# Sheet1.net
KiCad netlist of a schematic drawn in Altium Designer
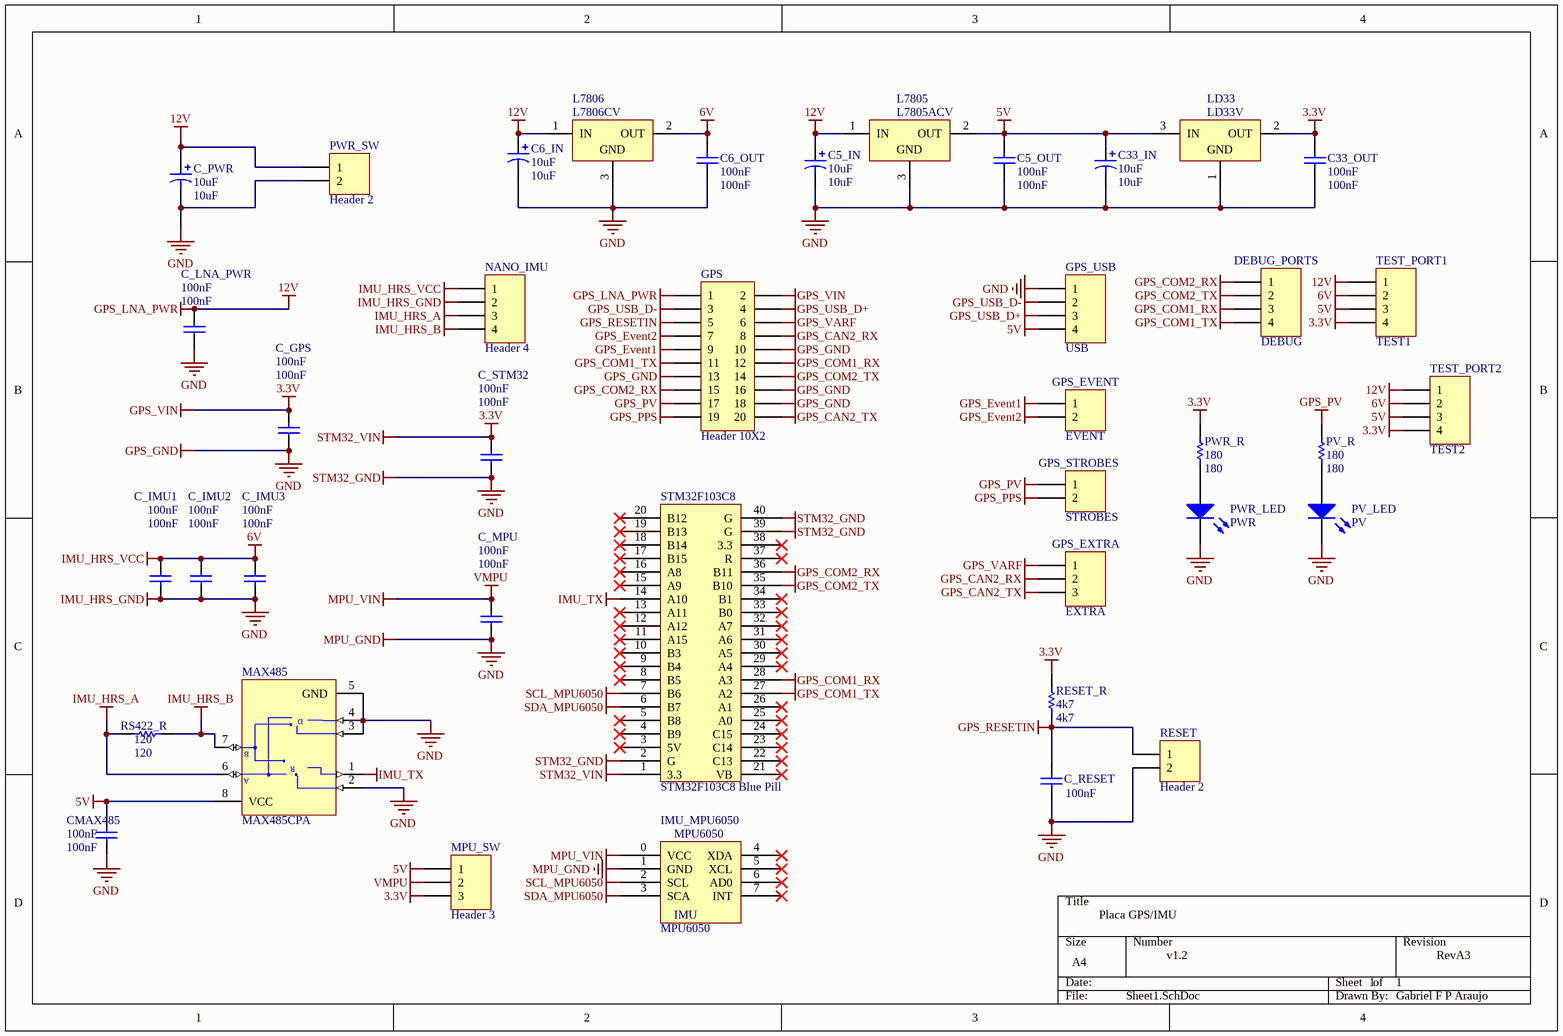
[diagram p0: Sheet1.SchDoc]

(export (version "E")
  (design (tool "Eeschema 10.0.6"))
  (components
    (comp (ref "C5_IN")
      (value "10uF")
      (footprint "Capacitor1")
      (description "Polarized Capacitor (Radial)")
      (fields (field (name "ALTIUM_VALUE") "10uF") (field (name "PUBLISHER") "Altium Limited"))
      (libsource (lib "Miscellaneous Devices") (part "Cap Pol1"))
    )
    (comp (ref "C5_OUT")
      (value "100nF")
      (footprint "C_NANO_HOLES")
      (description "Capacitor")
      (fields (field (name "ALTIUM_VALUE") "100nF") (field (name "PUBLISHER") "Altium Limited"))
      (libsource (lib "Miscellaneous Devices") (part "Cap"))
    )
    (comp (ref "C6_IN")
      (value "10uF")
      (footprint "Capacitor1")
      (description "Polarized Capacitor (Radial)")
      (fields (field (name "ALTIUM_VALUE") "10uF") (field (name "PUBLISHER") "Altium Limited"))
      (libsource (lib "Miscellaneous Devices") (part "Cap Pol1"))
    )
    (comp (ref "C6_OUT")
      (value "100nF")
      (footprint "C_NANO_HOLES")
      (description "Capacitor")
      (fields (field (name "ALTIUM_VALUE") "100nF") (field (name "PUBLISHER") "Altium Limited"))
      (libsource (lib "Miscellaneous Devices") (part "Cap"))
    )
    (comp (ref "C33_IN")
      (value "10uF")
      (footprint "Capacitor1")
      (description "Polarized Capacitor (Radial)")
      (fields (field (name "ALTIUM_VALUE") "10uF") (field (name "PUBLISHER") "Altium Limited"))
      (libsource (lib "Miscellaneous Devices") (part "Cap Pol1"))
    )
    (comp (ref "C33_OUT")
      (value "100nF")
      (footprint "C_NANO_HOLES")
      (description "Capacitor")
      (fields (field (name "ALTIUM_VALUE") "100nF") (field (name "PUBLISHER") "Altium Limited"))
      (libsource (lib "Miscellaneous Devices") (part "Cap"))
    )
    (comp (ref "CMAX485")
      (value "100nF")
      (footprint "C_NANO_HOLES")
      (description "Capacitor")
      (fields (field (name "ALTIUM_VALUE") "100nF") (field (name "PUBLISHER") "Altium Limited"))
      (libsource (lib "Miscellaneous Devices") (part "Cap"))
    )
    (comp (ref "C_GPS")
      (value "100nF")
      (footprint "C_NANO_HOLES")
      (description "Capacitor")
      (fields (field (name "ALTIUM_VALUE") "100nF") (field (name "PUBLISHER") "Altium Limited"))
      (libsource (lib "Miscellaneous Devices") (part "Cap"))
    )
    (comp (ref "C_IMU1")
      (value "100nF")
      (footprint "C_NANO_HOLES")
      (description "Capacitor")
      (fields (field (name "ALTIUM_VALUE") "100nF") (field (name "PUBLISHER") "Altium Limited"))
      (libsource (lib "Miscellaneous Devices") (part "Cap"))
    )
    (comp (ref "C_IMU2")
      (value "100nF")
      (footprint "C_NANO_HOLES")
      (description "Capacitor")
      (fields (field (name "ALTIUM_VALUE") "100nF") (field (name "PUBLISHER") "Altium Limited"))
      (libsource (lib "Miscellaneous Devices") (part "Cap"))
    )
    (comp (ref "C_IMU3")
      (value "100nF")
      (footprint "C_NANO_HOLES")
      (description "Capacitor")
      (fields (field (name "ALTIUM_VALUE") "100nF") (field (name "PUBLISHER") "Altium Limited"))
      (libsource (lib "Miscellaneous Devices") (part "Cap"))
    )
    (comp (ref "C_LNA_PWR")
      (value "100nF")
      (footprint "C_NANO_HOLES")
      (description "Capacitor")
      (fields (field (name "ALTIUM_VALUE") "100nF") (field (name "PUBLISHER") "Altium Limited"))
      (libsource (lib "Miscellaneous Devices") (part "Cap"))
    )
    (comp (ref "C_MPU")
      (value "100nF")
      (footprint "C_NANO_HOLES")
      (description "Capacitor")
      (fields (field (name "ALTIUM_VALUE") "100nF") (field (name "PUBLISHER") "Altium Limited"))
      (libsource (lib "Miscellaneous Devices") (part "Cap"))
    )
    (comp (ref "C_PWR")
      (value "10uF")
      (footprint "Capacitor1")
      (description "Polarized Capacitor (Radial)")
      (fields (field (name "ALTIUM_VALUE") "10uF") (field (name "PUBLISHER") "Altium Limited"))
      (libsource (lib "Miscellaneous Devices") (part "Cap Pol1"))
    )
    (comp (ref "C_RESET")
      (value "100nF")
      (footprint "C_NANO_HOLES")
      (description "Capacitor")
      (fields (field (name "PUBLISHER") "Altium Limited"))
      (libsource (lib "Miscellaneous Devices") (part "Cap"))
    )
    (comp (ref "C_STM32")
      (value "100nF")
      (footprint "C_NANO_HOLES")
      (description "Capacitor")
      (fields (field (name "ALTIUM_VALUE") "100nF") (field (name "PUBLISHER") "Altium Limited"))
      (libsource (lib "Miscellaneous Devices") (part "Cap"))
    )
    (comp (ref "DEBUG_PORTS")
      (value "DEBUG")
      (footprint "HDR1X4")
      (description "Header, 4-Pin")
      (fields (field (name "PUBLISHER") "Altium Limited"))
      (libsource (lib "Miscellaneous Connectors") (part "Header 4"))
    )
    (comp (ref "GPS")
      (value "Header 10X2")
      (footprint "HDR2x10_2mm")
      (description "Header, 10-Pin, Dual row")
      (fields (field (name "PUBLISHER") "Altium Limited"))
      (libsource (lib "Miscellaneous Connectors") (part "Header 10X2"))
    )
    (comp (ref "GPS_EVENT")
      (value "EVENT")
      (footprint "HDR1X2")
      (description "Header, 2-Pin")
      (fields (field (name "PUBLISHER") "Altium Limited"))
      (libsource (lib "Miscellaneous Connectors") (part "Header 2"))
    )
    (comp (ref "GPS_EXTRA")
      (value "EXTRA")
      (footprint "HDR1X3")
      (description "Header, 3-Pin")
      (fields (field (name "PUBLISHER") "Altium Limited"))
      (libsource (lib "Miscellaneous Connectors") (part "Header 3"))
    )
    (comp (ref "GPS_STROBES")
      (value "STROBES")
      (footprint "HDR1X2")
      (description "Header, 2-Pin")
      (fields (field (name "PUBLISHER") "Altium Limited"))
      (libsource (lib "Miscellaneous Connectors") (part "Header 2"))
    )
    (comp (ref "GPS_USB")
      (value "USB")
      (footprint "HDR1X4")
      (description "Header, 4-Pin")
      (fields (field (name "PUBLISHER") "Altium Limited"))
      (libsource (lib "Miscellaneous Connectors") (part "Header 4"))
    )
    (comp (ref "IMU_MPU6050")
      (value "MPU6050")
      (footprint "MPU6050")
      (libsource (lib "IMU_MPU6050") (part "Component_1"))
    )
    (comp (ref "L7805")
      (value "L7805ACV")
      (footprint "TO220ABN")
      (description "Precision 1A Regulator")
      (fields (field (name "PUBLISHER") "Altium Limited"))
      (libsource (lib "ST Power Mgt Voltage Regulator") (part "L7805ACV"))
    )
    (comp (ref "L7806")
      (value "L7806CV")
      (footprint "TO220ABN")
      (description "Positive Voltage Regulator")
      (fields (field (name "PUBLISHER") "Altium Limited"))
      (libsource (lib "ST Power Mgt Voltage Regulator") (part "L7806CV"))
    )
    (comp (ref "LD33")
      (value "LD33V")
      (footprint "T03B")
      (description "800mA Low-Dropout Linear Regulator")
      (fields
        (field (name "PARTNUMBER") "LM1117T-3.3")
        (field (name "MANUFACTURER") "National Semiconductor")
        (field (name "PUBLISHER") "Altium Limited")
      )
      (libsource (lib "NSC LDO") (part "LM1117T-3.3"))
    )
    (comp (ref "MAX485")
      (value "MAX485CPA")
      (footprint "PA8")
      (description "Low-Power, Slew-Rate-Limited RS-485/RS-422 Transceiver")
      (fields (field (name "PUBLISHER") "Altium Limited"))
      (libsource (lib "Maxim Communication Transceiver") (part "MAX485CPA"))
    )
    (comp (ref "MPU_SW")
      (value "Header 3")
      (footprint "HDR1X3")
      (description "Header, 3-Pin")
      (fields (field (name "PUBLISHER") "Altium Limited"))
      (libsource (lib "Miscellaneous Connectors") (part "Header 3"))
    )
    (comp (ref "NANO_IMU")
      (value "Header 4")
      (footprint "HDR1X4")
      (description "Header, 4-Pin")
      (fields (field (name "PUBLISHER") "Altium Limited"))
      (libsource (lib "Miscellaneous Connectors") (part "Header 4"))
    )
    (comp (ref "PV_LED")
      (value "PV")
      (footprint "HDR1X2")
      (description "Typical INFRARED GaAs LED")
      (fields (field (name "PUBLISHER") "Altium Limited"))
      (libsource (lib "Miscellaneous Devices") (part "LED0"))
    )
    (comp (ref "PV_R")
      (value "180")
      (footprint "AXIAL-0.3")
      (description "Resistor")
      (fields (field (name "ALTIUM_VALUE") "180") (field (name "PUBLISHER") "Altium Limited"))
      (libsource (lib "Miscellaneous Devices") (part "Res1"))
    )
    (comp (ref "PWR_LED")
      (value "PWR")
      (footprint "HDR1X2")
      (description "Typical INFRARED GaAs LED")
      (fields (field (name "PUBLISHER") "Altium Limited"))
      (libsource (lib "Miscellaneous Devices") (part "LED0"))
    )
    (comp (ref "PWR_R")
      (value "180")
      (footprint "AXIAL-0.3")
      (description "Resistor")
      (fields (field (name "ALTIUM_VALUE") "180") (field (name "PUBLISHER") "Altium Limited"))
      (libsource (lib "Miscellaneous Devices") (part "Res1"))
    )
    (comp (ref "PWR_SW")
      (value "Header 2")
      (footprint "HDR1X2")
      (description "Header, 2-Pin")
      (fields (field (name "PUBLISHER") "Altium Limited"))
      (libsource (lib "Miscellaneous Connectors") (part "Header 2"))
    )
    (comp (ref "RESET")
      (value "Header 2")
      (footprint "HDR1X2")
      (description "Header, 2-Pin")
      (fields (field (name "PUBLISHER") "Altium Limited"))
      (libsource (lib "Miscellaneous Connectors") (part "Header 2"))
    )
    (comp (ref "RESET_R")
      (value "4k7")
      (footprint "AXIAL-0.3")
      (description "Resistor")
      (fields (field (name "ALTIUM_VALUE") "4k7") (field (name "PUBLISHER") "Altium Limited"))
      (libsource (lib "Miscellaneous Devices") (part "Res1"))
    )
    (comp (ref "RS422_R")
      (value "120")
      (footprint "AXIAL-0.3")
      (description "Resistor")
      (fields (field (name "ALTIUM_VALUE") "120") (field (name "PUBLISHER") "Altium Limited"))
      (libsource (lib "Miscellaneous Devices") (part "Res1"))
    )
    (comp (ref "STM32F103C8")
      (value "STM32F103C8 Blue Pill")
      (footprint "STM32F103C8")
      (libsource (lib "BluePill") (part "STM32F103C8"))
    )
    (comp (ref "TEST_PORT1")
      (value "TEST1")
      (footprint "HDR1X4")
      (description "Header, 4-Pin")
      (fields (field (name "PUBLISHER") "Altium Limited"))
      (libsource (lib "Miscellaneous Connectors") (part "Header 4"))
    )
    (comp (ref "TEST_PORT2")
      (value "TEST2")
      (footprint "HDR1X4")
      (description "Header, 4-Pin")
      (fields (field (name "PUBLISHER") "Altium Limited"))
      (libsource (lib "Miscellaneous Connectors") (part "Header 4"))
    )
  )
  (nets
    (net (code "1") (name "3.3V") (class "Default")
      (node (ref "C33_OUT") (pin "1") (pinfunction "1_1") (pintype "passive"))
      (node (ref "C_GPS") (pin "2") (pinfunction "2_2") (pintype "passive"))
      (node (ref "C_STM32") (pin "2") (pinfunction "2_2") (pintype "passive"))
      (node (ref "GPS") (pin "2") (pinfunction "2_2") (pintype "passive"))
      (node (ref "LD33") (pin "2") (pinfunction "OUT_2") (pintype "power_in"))
      (node (ref "MPU_SW") (pin "3") (pinfunction "3_3") (pintype "passive"))
      (node (ref "PWR_R") (pin "2") (pinfunction "2_2") (pintype "passive"))
      (node (ref "RESET_R") (pin "2") (pinfunction "2_2") (pintype "passive"))
      (node (ref "STM32F103C8") (pin "1") (pinfunction "3.3_1") (pintype "passive"))
      (node (ref "TEST_PORT1") (pin "4") (pinfunction "4_4") (pintype "passive"))
      (node (ref "TEST_PORT2") (pin "4") (pinfunction "4_4") (pintype "passive"))
    )
    (net (code "2") (name "5V") (class "Default")
      (node (ref "C33_IN") (pin "1") (pinfunction "1_1") (pintype "passive"))
      (node (ref "C5_OUT") (pin "1") (pinfunction "1_1") (pintype "passive"))
      (node (ref "CMAX485") (pin "2") (pinfunction "2_2") (pintype "passive"))
      (node (ref "GPS_USB") (pin "4") (pinfunction "4_4") (pintype "passive"))
      (node (ref "L7805") (pin "2") (pinfunction "OUT_2") (pintype "power_in"))
      (node (ref "LD33") (pin "3") (pinfunction "IN_3") (pintype "power_in"))
      (node (ref "MAX485") (pin "8") (pinfunction "VCC_8") (pintype "power_in"))
      (node (ref "MPU_SW") (pin "1") (pinfunction "1_1") (pintype "passive"))
      (node (ref "TEST_PORT1") (pin "3") (pinfunction "3_3") (pintype "passive"))
      (node (ref "TEST_PORT2") (pin "3") (pinfunction "3_3") (pintype "passive"))
    )
    (net (code "3") (name "6V") (class "Default")
      (node (ref "C6_OUT") (pin "1") (pinfunction "1_1") (pintype "passive"))
      (node (ref "C_IMU1") (pin "2") (pinfunction "2_2") (pintype "passive"))
      (node (ref "C_IMU2") (pin "2") (pinfunction "2_2") (pintype "passive"))
      (node (ref "C_IMU3") (pin "2") (pinfunction "2_2") (pintype "passive"))
      (node (ref "L7806") (pin "2") (pinfunction "OUT_2") (pintype "power_in"))
      (node (ref "NANO_IMU") (pin "1") (pinfunction "1_1") (pintype "passive"))
      (node (ref "TEST_PORT1") (pin "2") (pinfunction "2_2") (pintype "passive"))
      (node (ref "TEST_PORT2") (pin "2") (pinfunction "2_2") (pintype "passive"))
    )
    (net (code "4") (name "12V") (class "Default")
      (node (ref "C5_IN") (pin "1") (pinfunction "1_1") (pintype "passive"))
      (node (ref "C6_IN") (pin "1") (pinfunction "1_1") (pintype "passive"))
      (node (ref "C_LNA_PWR") (pin "2") (pinfunction "2_2") (pintype "passive"))
      (node (ref "C_PWR") (pin "1") (pinfunction "1_1") (pintype "passive"))
      (node (ref "GPS") (pin "1") (pinfunction "1_1") (pintype "passive"))
      (node (ref "L7805") (pin "1") (pinfunction "IN_1") (pintype "power_in"))
      (node (ref "L7806") (pin "1") (pinfunction "IN_1") (pintype "power_in"))
      (node (ref "PWR_SW") (pin "1") (pinfunction "1_1") (pintype "passive"))
      (node (ref "TEST_PORT1") (pin "1") (pinfunction "1_1") (pintype "passive"))
      (node (ref "TEST_PORT2") (pin "1") (pinfunction "1_1") (pintype "passive"))
    )
    (net (code "5") (name "GND") (class "Default")
      (node (ref "C33_IN") (pin "2") (pinfunction "2_2") (pintype "passive"))
      (node (ref "C33_OUT") (pin "2") (pinfunction "2_2") (pintype "passive"))
      (node (ref "C5_IN") (pin "2") (pinfunction "2_2") (pintype "passive"))
      (node (ref "C5_OUT") (pin "2") (pinfunction "2_2") (pintype "passive"))
      (node (ref "C6_IN") (pin "2") (pinfunction "2_2") (pintype "passive"))
      (node (ref "C6_OUT") (pin "2") (pinfunction "2_2") (pintype "passive"))
      (node (ref "CMAX485") (pin "1") (pinfunction "1_1") (pintype "passive"))
      (node (ref "C_GPS") (pin "1") (pinfunction "1_1") (pintype "passive"))
      (node (ref "C_IMU1") (pin "1") (pinfunction "1_1") (pintype "passive"))
      (node (ref "C_IMU2") (pin "1") (pinfunction "1_1") (pintype "passive"))
      (node (ref "C_IMU3") (pin "1") (pinfunction "1_1") (pintype "passive"))
      (node (ref "C_LNA_PWR") (pin "1") (pinfunction "1_1") (pintype "passive"))
      (node (ref "C_MPU") (pin "1") (pinfunction "1_1") (pintype "passive"))
      (node (ref "C_PWR") (pin "2") (pinfunction "2_2") (pintype "passive"))
      (node (ref "C_RESET") (pin "1") (pinfunction "1_1") (pintype "passive"))
      (node (ref "C_STM32") (pin "1") (pinfunction "1_1") (pintype "passive"))
      (node (ref "GPS") (pin "10") (pinfunction "10_10") (pintype "passive"))
      (node (ref "GPS") (pin "13") (pinfunction "13_13") (pintype "passive"))
      (node (ref "GPS") (pin "16") (pinfunction "16_16") (pintype "passive"))
      (node (ref "GPS") (pin "18") (pinfunction "18_18") (pintype "passive"))
      (node (ref "GPS_USB") (pin "1") (pinfunction "1_1") (pintype "passive"))
      (node (ref "IMU_MPU6050") (pin "1") (pinfunction "GND_1") (pintype "passive"))
      (node (ref "L7805") (pin "3") (pinfunction "GND_3") (pintype "power_in"))
      (node (ref "L7806") (pin "3") (pinfunction "GND_3") (pintype "power_in"))
      (node (ref "LD33") (pin "1") (pinfunction "GND_1") (pintype "power_in"))
      (node (ref "MAX485") (pin "2") (pinfunction "~{RE}_2") (pintype "input"))
      (node (ref "MAX485") (pin "3") (pinfunction "DE_3") (pintype "input"))
      (node (ref "MAX485") (pin "4") (pinfunction "DI_4") (pintype "input"))
      (node (ref "MAX485") (pin "5") (pinfunction "GND_5") (pintype "power_in"))
      (node (ref "NANO_IMU") (pin "2") (pinfunction "2_2") (pintype "passive"))
      (node (ref "PV_LED") (pin "2") (pinfunction "K_2") (pintype "passive"))
      (node (ref "PWR_LED") (pin "2") (pinfunction "K_2") (pintype "passive"))
      (node (ref "PWR_SW") (pin "2") (pinfunction "2_2") (pintype "passive"))
      (node (ref "RESET") (pin "2") (pinfunction "2_2") (pintype "passive"))
      (node (ref "STM32F103C8") (pin "2") (pinfunction "G_2") (pintype "passive"))
      (node (ref "STM32F103C8") (pin "39") (pinfunction "G_39") (pintype "passive"))
      (node (ref "STM32F103C8") (pin "40") (pinfunction "G_40") (pintype "passive"))
    )
    (net (code "6") (name "GPS_CAN2_RX") (class "Default")
      (node (ref "GPS") (pin "8") (pinfunction "8_8") (pintype "passive"))
      (node (ref "GPS_EXTRA") (pin "2") (pinfunction "2_2") (pintype "passive"))
    )
    (net (code "7") (name "GPS_CAN2_TX") (class "Default")
      (node (ref "GPS") (pin "20") (pinfunction "20_20") (pintype "passive"))
      (node (ref "GPS_EXTRA") (pin "3") (pinfunction "3_3") (pintype "passive"))
    )
    (net (code "8") (name "GPS_COM1_RX") (class "Default")
      (node (ref "DEBUG_PORTS") (pin "3") (pinfunction "3_3") (pintype "passive"))
      (node (ref "GPS") (pin "12") (pinfunction "12_12") (pintype "passive"))
      (node (ref "STM32F103C8") (pin "28") (pinfunction "A3_28") (pintype "passive"))
    )
    (net (code "9") (name "GPS_COM1_TX") (class "Default")
      (node (ref "DEBUG_PORTS") (pin "4") (pinfunction "4_4") (pintype "passive"))
      (node (ref "GPS") (pin "11") (pinfunction "11_11") (pintype "passive"))
      (node (ref "STM32F103C8") (pin "27") (pinfunction "A2_27") (pintype "passive"))
    )
    (net (code "10") (name "GPS_COM2_RX") (class "Default")
      (node (ref "DEBUG_PORTS") (pin "1") (pinfunction "1_1") (pintype "passive"))
      (node (ref "GPS") (pin "15") (pinfunction "15_15") (pintype "passive"))
      (node (ref "STM32F103C8") (pin "36") (pinfunction "B11_36") (pintype "passive"))
    )
    (net (code "11") (name "GPS_COM2_TX") (class "Default")
      (node (ref "DEBUG_PORTS") (pin "2") (pinfunction "2_2") (pintype "passive"))
      (node (ref "GPS") (pin "14") (pinfunction "14_14") (pintype "passive"))
      (node (ref "STM32F103C8") (pin "35") (pinfunction "B10_35") (pintype "passive"))
    )
    (net (code "12") (name "GPS_Event1") (class "Default")
      (node (ref "GPS") (pin "9") (pinfunction "9_9") (pintype "passive"))
      (node (ref "GPS_EVENT") (pin "1") (pinfunction "1_1") (pintype "passive"))
    )
    (net (code "13") (name "GPS_Event2") (class "Default")
      (node (ref "GPS") (pin "7") (pinfunction "7_7") (pintype "passive"))
      (node (ref "GPS_EVENT") (pin "2") (pinfunction "2_2") (pintype "passive"))
    )
    (net (code "14") (name "GPS_PPS") (class "Default")
      (node (ref "GPS") (pin "19") (pinfunction "19_19") (pintype "passive"))
      (node (ref "GPS_STROBES") (pin "2") (pinfunction "2_2") (pintype "passive"))
    )
    (net (code "15") (name "GPS_PV") (class "Default")
      (node (ref "GPS") (pin "17") (pinfunction "17_17") (pintype "passive"))
      (node (ref "GPS_STROBES") (pin "1") (pinfunction "1_1") (pintype "passive"))
      (node (ref "PV_R") (pin "2") (pinfunction "2_2") (pintype "passive"))
    )
    (net (code "16") (name "GPS_RESETIN") (class "Default")
      (node (ref "C_RESET") (pin "2") (pinfunction "2_2") (pintype "passive"))
      (node (ref "GPS") (pin "5") (pinfunction "5_5") (pintype "passive"))
      (node (ref "RESET") (pin "1") (pinfunction "1_1") (pintype "passive"))
      (node (ref "RESET_R") (pin "1") (pinfunction "1_1") (pintype "passive"))
    )
    (net (code "17") (name "GPS_USB_D+") (class "Default")
      (node (ref "GPS") (pin "4") (pinfunction "4_4") (pintype "passive"))
      (node (ref "GPS_USB") (pin "3") (pinfunction "3_3") (pintype "passive"))
    )
    (net (code "18") (name "GPS_USB_D-") (class "Default")
      (node (ref "GPS") (pin "3") (pinfunction "3_3") (pintype "passive"))
      (node (ref "GPS_USB") (pin "2") (pinfunction "2_2") (pintype "passive"))
    )
    (net (code "19") (name "GPS_VARF") (class "Default")
      (node (ref "GPS") (pin "6") (pinfunction "6_6") (pintype "passive"))
      (node (ref "GPS_EXTRA") (pin "1") (pinfunction "1_1") (pintype "passive"))
    )
    (net (code "20") (name "IMU_HRS_A") (class "Default")
      (node (ref "MAX485") (pin "6") (pinfunction "A_6") (pintype "bidirectional"))
      (node (ref "NANO_IMU") (pin "3") (pinfunction "3_3") (pintype "passive"))
      (node (ref "RS422_R") (pin "1") (pinfunction "1_1") (pintype "passive"))
    )
    (net (code "21") (name "IMU_HRS_B") (class "Default")
      (node (ref "MAX485") (pin "7") (pinfunction "B_7") (pintype "bidirectional"))
      (node (ref "NANO_IMU") (pin "4") (pinfunction "4_4") (pintype "passive"))
      (node (ref "RS422_R") (pin "2") (pinfunction "2_2") (pintype "passive"))
    )
    (net (code "22") (name "IMU_TX") (class "Default")
      (node (ref "MAX485") (pin "1") (pinfunction "RO_1") (pintype "output"))
      (node (ref "STM32F103C8") (pin "14") (pinfunction "A10_14") (pintype "passive"))
    )
    (net (code "23") (name "MPU_VIN") (class "Default")
      (node (ref "C_MPU") (pin "2") (pinfunction "2_2") (pintype "passive"))
      (node (ref "IMU_MPU6050") (pin "0") (pinfunction "VCC_0") (pintype "passive"))
      (node (ref "MPU_SW") (pin "2") (pinfunction "2_2") (pintype "passive"))
    )
    (net (code "24") (name "Net-(PV_LED-A)") (class "Default")
      (node (ref "PV_LED") (pin "1") (pinfunction "A_1") (pintype "passive"))
      (node (ref "PV_R") (pin "1") (pinfunction "1_1") (pintype "passive"))
    )
    (net (code "25") (name "Net-(PWR_LED-A)") (class "Default")
      (node (ref "PWR_LED") (pin "1") (pinfunction "A_1") (pintype "passive"))
      (node (ref "PWR_R") (pin "1") (pinfunction "1_1") (pintype "passive"))
    )
    (net (code "26") (name "SCL_MPU6050") (class "Default")
      (node (ref "IMU_MPU6050") (pin "2") (pinfunction "SCL_2") (pintype "passive"))
      (node (ref "STM32F103C8") (pin "7") (pinfunction "B6_7") (pintype "passive"))
    )
    (net (code "27") (name "SDA_MPU6050") (class "Default")
      (node (ref "IMU_MPU6050") (pin "3") (pinfunction "SCA_3") (pintype "passive"))
      (node (ref "STM32F103C8") (pin "6") (pinfunction "B7_6") (pintype "passive"))
    )
    (net (code "28") (name "unconnected-(IMU_MPU6050-AD0-Pad6)") (class "Default")
      (node (ref "IMU_MPU6050") (pin "6") (pinfunction "AD0_6") (pintype "passive+no_connect"))
    )
    (net (code "29") (name "unconnected-(IMU_MPU6050-INT-Pad7)") (class "Default")
      (node (ref "IMU_MPU6050") (pin "7") (pinfunction "INT_7") (pintype "passive+no_connect"))
    )
    (net (code "30") (name "unconnected-(IMU_MPU6050-XCL-Pad5)") (class "Default")
      (node (ref "IMU_MPU6050") (pin "5") (pinfunction "XCL_5") (pintype "passive+no_connect"))
    )
    (net (code "31") (name "unconnected-(IMU_MPU6050-XDA-Pad4)") (class "Default")
      (node (ref "IMU_MPU6050") (pin "4") (pinfunction "XDA_4") (pintype "passive+no_connect"))
    )
    (net (code "32") (name "unconnected-(STM32F103C8-3.3-Pad38)") (class "Default")
      (node (ref "STM32F103C8") (pin "38") (pinfunction "3.3_38") (pintype "passive+no_connect"))
    )
    (net (code "33") (name "unconnected-(STM32F103C8-5V-Pad3)") (class "Default")
      (node (ref "STM32F103C8") (pin "3") (pinfunction "5V_3") (pintype "passive+no_connect"))
    )
    (net (code "34") (name "unconnected-(STM32F103C8-A0-Pad25)") (class "Default")
      (node (ref "STM32F103C8") (pin "25") (pinfunction "A0_25") (pintype "passive+no_connect"))
    )
    (net (code "35") (name "unconnected-(STM32F103C8-A1-Pad26)") (class "Default")
      (node (ref "STM32F103C8") (pin "26") (pinfunction "A1_26") (pintype "passive+no_connect"))
    )
    (net (code "36") (name "unconnected-(STM32F103C8-A4-Pad29)") (class "Default")
      (node (ref "STM32F103C8") (pin "29") (pinfunction "A4_29") (pintype "passive+no_connect"))
    )
    (net (code "37") (name "unconnected-(STM32F103C8-A5-Pad30)") (class "Default")
      (node (ref "STM32F103C8") (pin "30") (pinfunction "A5_30") (pintype "passive+no_connect"))
    )
    (net (code "38") (name "unconnected-(STM32F103C8-A6-Pad31)") (class "Default")
      (node (ref "STM32F103C8") (pin "31") (pinfunction "A6_31") (pintype "passive+no_connect"))
    )
    (net (code "39") (name "unconnected-(STM32F103C8-A7-Pad32)") (class "Default")
      (node (ref "STM32F103C8") (pin "32") (pinfunction "A7_32") (pintype "passive+no_connect"))
    )
    (net (code "40") (name "unconnected-(STM32F103C8-A8-Pad16)") (class "Default")
      (node (ref "STM32F103C8") (pin "16") (pinfunction "A8_16") (pintype "passive+no_connect"))
    )
    (net (code "41") (name "unconnected-(STM32F103C8-A9-Pad15)") (class "Default")
      (node (ref "STM32F103C8") (pin "15") (pinfunction "A9_15") (pintype "passive+no_connect"))
    )
    (net (code "42") (name "unconnected-(STM32F103C8-A11-Pad13)") (class "Default")
      (node (ref "STM32F103C8") (pin "13") (pinfunction "A11_13") (pintype "passive+no_connect"))
    )
    (net (code "43") (name "unconnected-(STM32F103C8-A12-Pad12)") (class "Default")
      (node (ref "STM32F103C8") (pin "12") (pinfunction "A12_12") (pintype "passive+no_connect"))
    )
    (net (code "44") (name "unconnected-(STM32F103C8-A15-Pad11)") (class "Default")
      (node (ref "STM32F103C8") (pin "11") (pinfunction "A15_11") (pintype "passive+no_connect"))
    )
    (net (code "45") (name "unconnected-(STM32F103C8-B0-Pad33)") (class "Default")
      (node (ref "STM32F103C8") (pin "33") (pinfunction "B0_33") (pintype "passive+no_connect"))
    )
    (net (code "46") (name "unconnected-(STM32F103C8-B1-Pad34)") (class "Default")
      (node (ref "STM32F103C8") (pin "34") (pinfunction "B1_34") (pintype "passive+no_connect"))
    )
    (net (code "47") (name "unconnected-(STM32F103C8-B3-Pad10)") (class "Default")
      (node (ref "STM32F103C8") (pin "10") (pinfunction "B3_10") (pintype "passive+no_connect"))
    )
    (net (code "48") (name "unconnected-(STM32F103C8-B4-Pad9)") (class "Default")
      (node (ref "STM32F103C8") (pin "9") (pinfunction "B4_9") (pintype "passive+no_connect"))
    )
    (net (code "49") (name "unconnected-(STM32F103C8-B5-Pad8)") (class "Default")
      (node (ref "STM32F103C8") (pin "8") (pinfunction "B5_8") (pintype "passive+no_connect"))
    )
    (net (code "50") (name "unconnected-(STM32F103C8-B8-Pad5)") (class "Default")
      (node (ref "STM32F103C8") (pin "5") (pinfunction "B8_5") (pintype "passive+no_connect"))
    )
    (net (code "51") (name "unconnected-(STM32F103C8-B9-Pad4)") (class "Default")
      (node (ref "STM32F103C8") (pin "4") (pinfunction "B9_4") (pintype "passive+no_connect"))
    )
    (net (code "52") (name "unconnected-(STM32F103C8-B12-Pad20)") (class "Default")
      (node (ref "STM32F103C8") (pin "20") (pinfunction "B12_20") (pintype "passive+no_connect"))
    )
    (net (code "53") (name "unconnected-(STM32F103C8-B13-Pad19)") (class "Default")
      (node (ref "STM32F103C8") (pin "19") (pinfunction "B13_19") (pintype "passive+no_connect"))
    )
    (net (code "54") (name "unconnected-(STM32F103C8-B14-Pad18)") (class "Default")
      (node (ref "STM32F103C8") (pin "18") (pinfunction "B14_18") (pintype "passive+no_connect"))
    )
    (net (code "55") (name "unconnected-(STM32F103C8-B15-Pad17)") (class "Default")
      (node (ref "STM32F103C8") (pin "17") (pinfunction "B15_17") (pintype "passive+no_connect"))
    )
    (net (code "56") (name "unconnected-(STM32F103C8-C13-Pad22)") (class "Default")
      (node (ref "STM32F103C8") (pin "22") (pinfunction "C13_22") (pintype "passive+no_connect"))
    )
    (net (code "57") (name "unconnected-(STM32F103C8-C14-Pad23)") (class "Default")
      (node (ref "STM32F103C8") (pin "23") (pinfunction "C14_23") (pintype "passive+no_connect"))
    )
    (net (code "58") (name "unconnected-(STM32F103C8-C15-Pad24)") (class "Default")
      (node (ref "STM32F103C8") (pin "24") (pinfunction "C15_24") (pintype "passive+no_connect"))
    )
    (net (code "59") (name "unconnected-(STM32F103C8-R-Pad37)") (class "Default")
      (node (ref "STM32F103C8") (pin "37") (pinfunction "R_37") (pintype "passive+no_connect"))
    )
    (net (code "60") (name "unconnected-(STM32F103C8-VB-Pad21)") (class "Default")
      (node (ref "STM32F103C8") (pin "21") (pinfunction "VB_21") (pintype "passive+no_connect"))
    )
  )
)
